# HF.net
KiCad netlist of a schematic drawn in EAGLE
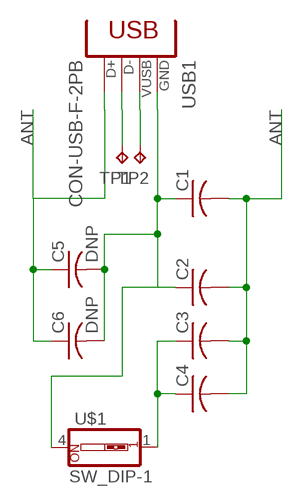
[diagram p0: schematic, sheet 1]

(export (version "E")
  (design (tool "Eeschema 10.0.6"))
  (components
    (comp (ref "C1")
      (value "C-USC1206")
      (footprint "eagle-import:C1206")
      (libsource (lib "eagle-import") (part "C-USC1206"))
    )
    (comp (ref "C2")
      (value "C-USC1206")
      (footprint "eagle-import:C1206")
      (libsource (lib "eagle-import") (part "C-USC1206"))
    )
    (comp (ref "C3")
      (value "C-USC1206")
      (footprint "eagle-import:C1206")
      (libsource (lib "eagle-import") (part "C-USC1206"))
    )
    (comp (ref "C4")
      (value "C-USC1206")
      (footprint "eagle-import:C1206")
      (libsource (lib "eagle-import") (part "C-USC1206"))
    )
    (comp (ref "C5")
      (value "DNP")
      (footprint "eagle-import:C1206")
      (libsource (lib "eagle-import") (part "C-USC1206"))
    )
    (comp (ref "C6")
      (value "DNP")
      (footprint "eagle-import:C1206")
      (libsource (lib "eagle-import") (part "C-USC1206"))
    )
    (comp (ref "TP1")
      (value "TPPAD1-13")
      (footprint "eagle-import:P1-13")
      (libsource (lib "eagle-import") (part "TPPAD1-13"))
    )
    (comp (ref "TP2")
      (value "TPPAD1-13")
      (footprint "eagle-import:P1-13")
      (libsource (lib "eagle-import") (part "TPPAD1-13"))
    )
    (comp (ref "U$1")
      (value "SW_DIP-1")
      (footprint "eagle-import:DIPSWITCH-01")
      (libsource (lib "eagle-import") (part "SW_DIP-1"))
    )
    (comp (ref "USB1")
      (value "CON-USB-F-2PB")
      (footprint "eagle-import:CONN_USB_A_F")
      (libsource (lib "eagle-import") (part "CON-USB-F-2PB"))
    )
  )
  (nets
    (net (code "1") (name "/ANT") (class "Default")
      (node (ref "C1") (pin "2") (pinfunction "2_2") (pintype "passive"))
      (node (ref "C2") (pin "2") (pinfunction "2_2") (pintype "passive"))
      (node (ref "C3") (pin "2") (pinfunction "2_2") (pintype "passive"))
      (node (ref "C4") (pin "2") (pinfunction "2_2") (pintype "passive"))
      (node (ref "C5") (pin "1") (pinfunction "1_1") (pintype "passive"))
      (node (ref "C6") (pin "1") (pinfunction "1_1") (pintype "passive"))
      (node (ref "USB1") (pin "3") (pinfunction "D+_3") (pintype "bidirectional"))
    )
    (net (code "2") (name "Net-(C3-Pad1)") (class "Default")
      (node (ref "C3") (pin "1") (pinfunction "1_1") (pintype "passive"))
      (node (ref "C4") (pin "1") (pinfunction "1_1") (pintype "passive"))
      (node (ref "U$1") (pin "1") (pinfunction "1_1") (pintype "passive"))
    )
    (net (code "3") (name "Net-(USB1B-D-)") (class "Default")
      (node (ref "TP1") (pin "TP") (pinfunction "TP_TP") (pintype "input"))
      (node (ref "USB1") (pin "2") (pinfunction "D-_2") (pintype "bidirectional"))
    )
    (net (code "4") (name "Net-(USB1B-GND)") (class "Default")
      (node (ref "C1") (pin "1") (pinfunction "1_1") (pintype "passive"))
      (node (ref "C2") (pin "1") (pinfunction "1_1") (pintype "passive"))
      (node (ref "C5") (pin "2") (pinfunction "2_2") (pintype "passive"))
      (node (ref "C6") (pin "2") (pinfunction "2_2") (pintype "passive"))
      (node (ref "U$1") (pin "4") (pinfunction "4_4") (pintype "passive"))
      (node (ref "USB1") (pin "4") (pinfunction "GND_4") (pintype "bidirectional"))
    )
    (net (code "5") (name "Net-(USB1B-VUSB)") (class "Default")
      (node (ref "TP2") (pin "TP") (pinfunction "TP_TP") (pintype "input"))
      (node (ref "USB1") (pin "1") (pinfunction "VUSB_1") (pintype "bidirectional"))
    )
  )
)
